# circuit.net
KiCad netlist of a schematic drawn in EAGLE
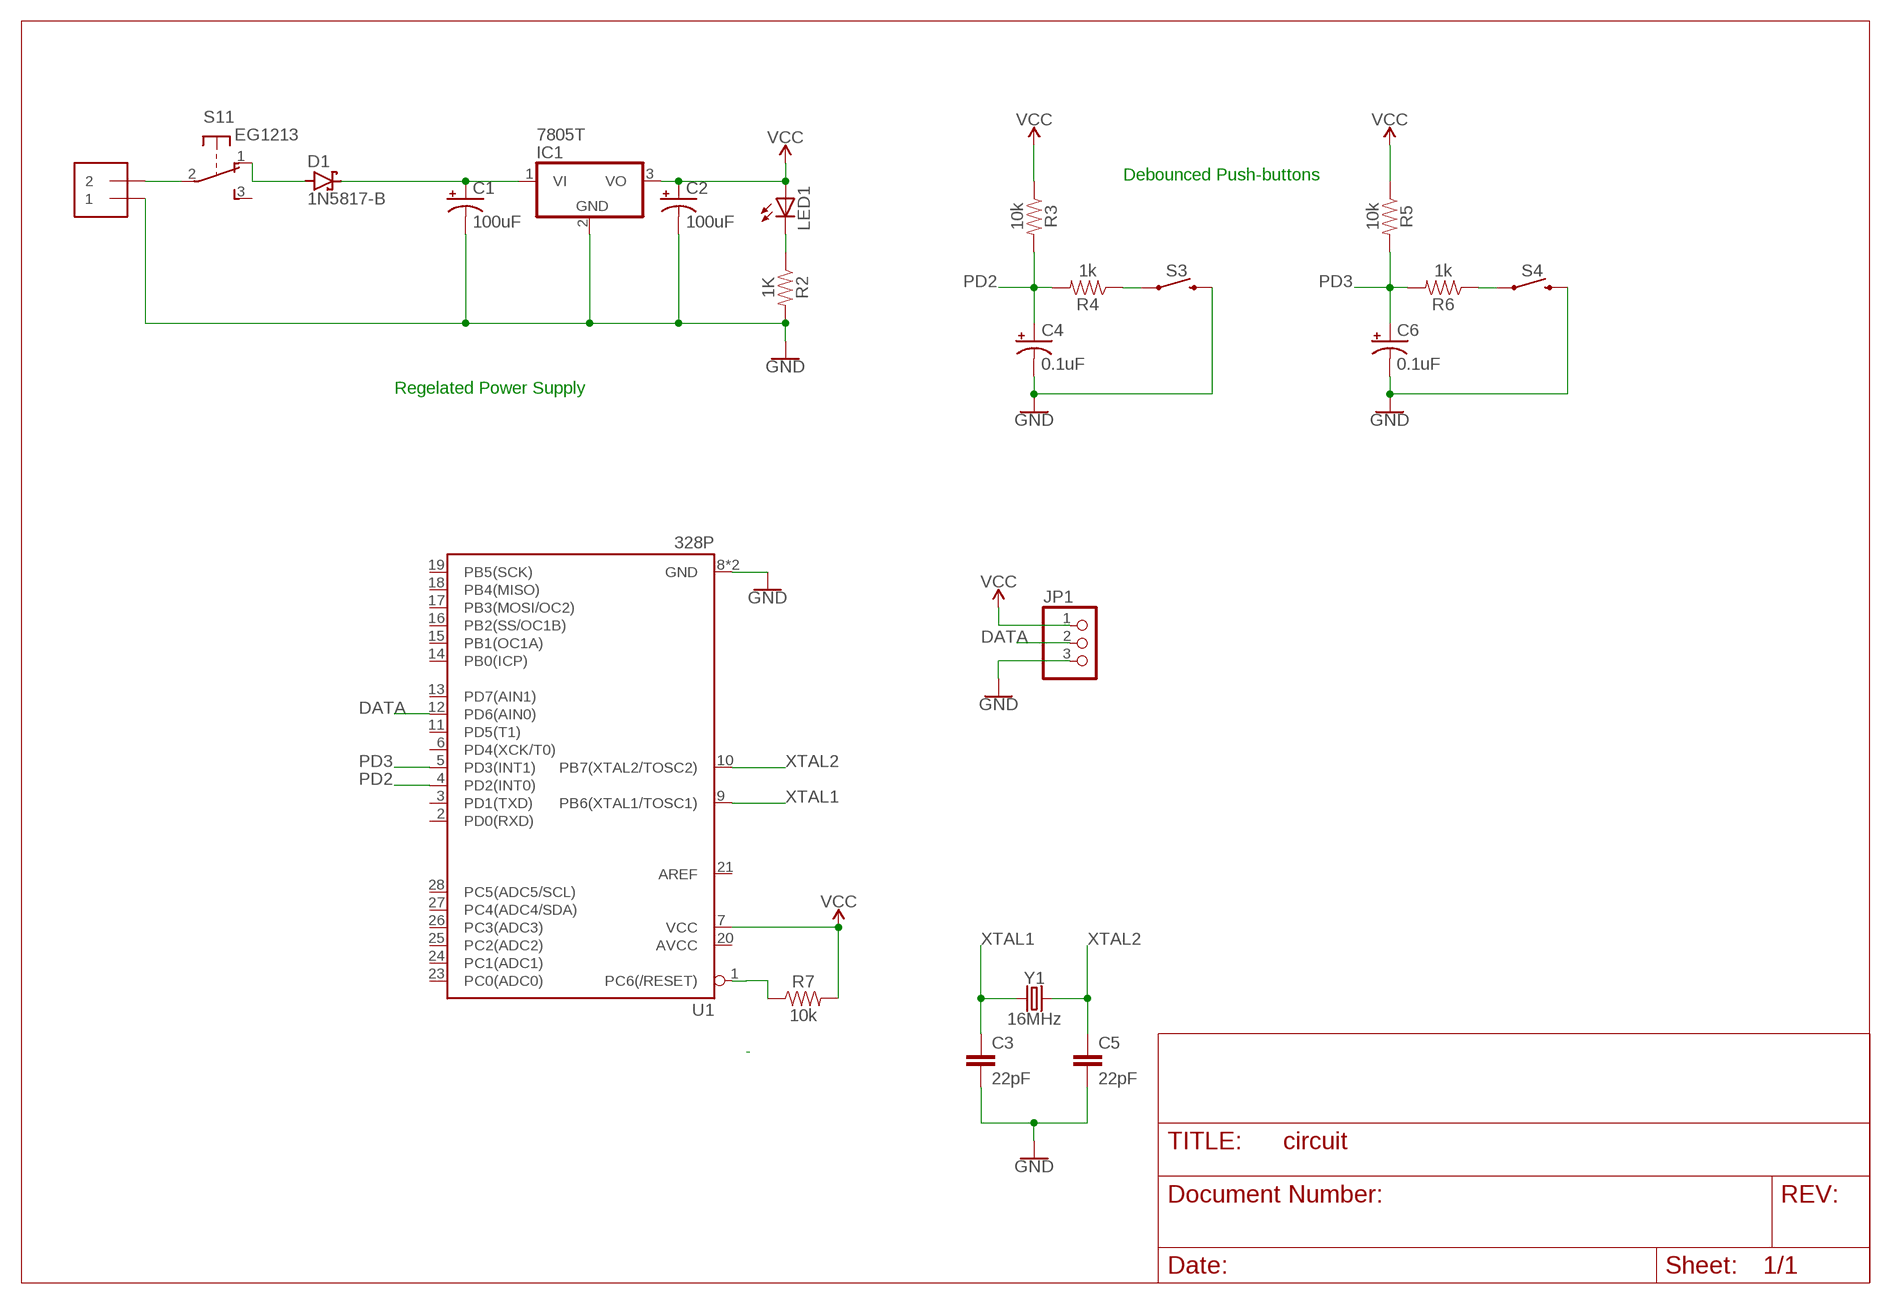
[diagram p0: schematic, sheet 1]

(export (version "E")
  (design (tool "Eeschema 10.0.6"))
  (components
    (comp (ref "C1")
      (value "100uF")
      (footprint "eagle-import:CPOL-RADIAL-2.5MM-6.5MM")
      (libsource (lib "eagle-import") (part "100UF-POLAR-RADIAL-2.5MM-25V-20%"))
    )
    (comp (ref "C2")
      (value "100uF")
      (footprint "eagle-import:CPOL-RADIAL-2.5MM-6.5MM")
      (libsource (lib "eagle-import") (part "100UF-POLAR-RADIAL-2.5MM-25V-20%"))
    )
    (comp (ref "C3")
      (value "22pF")
      (footprint "eagle-import:CAP-PTH-2.54")
      (libsource (lib "eagle-import") (part "22PF-PTH-2.54MM-200V-5%"))
    )
    (comp (ref "C4")
      (value "0.1uF")
      (footprint "eagle-import:CPOL-RADIAL-2.5MM-5MM")
      (libsource (lib "eagle-import") (part "10UF-POLAR-RADIAL-2.5MM-25V-20%"))
    )
    (comp (ref "C5")
      (value "22pF")
      (footprint "eagle-import:CAP-PTH-2.54")
      (libsource (lib "eagle-import") (part "22PF-PTH-2.54MM-200V-5%"))
    )
    (comp (ref "C6")
      (value "0.1uF")
      (footprint "eagle-import:CPOL-RADIAL-2.5MM-5MM")
      (libsource (lib "eagle-import") (part "10UF-POLAR-RADIAL-2.5MM-25V-20%"))
    )
    (comp (ref "D1")
      (value "1N5817-B")
      (footprint "eagle-import:DO41-7.6")
      (libsource (lib "eagle-import") (part "1N5817-B"))
    )
    (comp (ref "IC1")
      (value "7805T")
      (footprint "eagle-import:TO220H")
      (libsource (lib "eagle-import") (part "78T05"))
    )
    (comp (ref "J1")
      (value "1X2-3.5MM")
      (footprint "eagle-import:1X2-3.5MM")
      (libsource (lib "eagle-import") (part "1X2-3.5MM"))
    )
    (comp (ref "JP1")
      (value "PINHD-1X3")
      (footprint "eagle-import:1X03")
      (libsource (lib "eagle-import") (part "PINHD-1X3"))
    )
    (comp (ref "LED1")
      (value "LED3MM")
      (footprint "eagle-import:LED3MM")
      (libsource (lib "eagle-import") (part "LED3MM"))
    )
    (comp (ref "R2")
      (value "1K")
      (footprint "eagle-import:AXIAL-0.3")
      (libsource (lib "eagle-import") (part "RESISTORAXIAL-0.3"))
    )
    (comp (ref "R3")
      (value "10k")
      (footprint "eagle-import:AXIAL-0.3")
      (libsource (lib "eagle-import") (part "RESISTORAXIAL-0.3"))
    )
    (comp (ref "R4")
      (value "1k")
      (footprint "eagle-import:AXIAL-0.3")
      (libsource (lib "eagle-import") (part "RESISTORAXIAL-0.3"))
    )
    (comp (ref "R5")
      (value "10k")
      (footprint "eagle-import:AXIAL-0.3")
      (libsource (lib "eagle-import") (part "RESISTORAXIAL-0.3"))
    )
    (comp (ref "R6")
      (value "1k")
      (footprint "eagle-import:AXIAL-0.3")
      (libsource (lib "eagle-import") (part "RESISTORAXIAL-0.3"))
    )
    (comp (ref "R7")
      (value "10k")
      (footprint "eagle-import:AXIAL-0.3")
      (libsource (lib "eagle-import") (part "RESISTORAXIAL-0.3"))
    )
    (comp (ref "S1")
      (value "EG1213")
      (footprint "eagle-import:EG1213")
      (libsource (lib "eagle-import") (part "EG1213"))
    )
    (comp (ref "S3")
      (value "MOMENTARY-SWITCH-SPST-PTH-6.0MM")
      (footprint "eagle-import:TACTILE_SWITCH_PTH_6.0MM")
      (libsource (lib "eagle-import") (part "MOMENTARY-SWITCH-SPST-PTH-6.0MM"))
    )
    (comp (ref "S4")
      (value "MOMENTARY-SWITCH-SPST-PTH-6.0MM")
      (footprint "eagle-import:TACTILE_SWITCH_PTH_6.0MM")
      (libsource (lib "eagle-import") (part "MOMENTARY-SWITCH-SPST-PTH-6.0MM"))
    )
    (comp (ref "U1")
      (value "328P")
      (footprint "eagle-import:DIP28")
      (libsource (lib "eagle-import") (part "ATMEGA328P_PDIP"))
    )
    (comp (ref "Y1")
      (value "16MHz")
      (footprint "eagle-import:HC49US")
      (libsource (lib "eagle-import") (part "CRYSTAL-16MHZPTH-HC49US"))
    )
  )
  (nets
    (net (code "1") (name "/DATA") (class "Default")
      (node (ref "JP1") (pin "2") (pinfunction "2_2") (pintype "passive"))
      (node (ref "U1") (pin "12") (pinfunction "PD6(AIN0)_12") (pintype "bidirectional"))
    )
    (net (code "2") (name "/PD2") (class "Default")
      (node (ref "C4") (pin "1") (pinfunction "+_1") (pintype "passive"))
      (node (ref "R3") (pin "P$2") (pinfunction "2_P$2") (pintype "passive"))
      (node (ref "R4") (pin "P$2") (pinfunction "2_P$2") (pintype "passive"))
      (node (ref "U1") (pin "4") (pinfunction "PD2(INT0)_4") (pintype "bidirectional"))
    )
    (net (code "3") (name "/PD3") (class "Default")
      (node (ref "C6") (pin "1") (pinfunction "+_1") (pintype "passive"))
      (node (ref "R5") (pin "P$2") (pinfunction "2_P$2") (pintype "passive"))
      (node (ref "R6") (pin "P$2") (pinfunction "2_P$2") (pintype "passive"))
      (node (ref "U1") (pin "5") (pinfunction "PD3(INT1)_5") (pintype "bidirectional"))
    )
    (net (code "4") (name "/XTAL1") (class "Default")
      (node (ref "C3") (pin "1") (pinfunction "1_1") (pintype "passive"))
      (node (ref "U1") (pin "9") (pinfunction "PB6(XTAL1/TOSC1)_9") (pintype "bidirectional"))
      (node (ref "Y1") (pin "1") (pinfunction "1_1") (pintype "passive"))
    )
    (net (code "5") (name "/XTAL2") (class "Default")
      (node (ref "C5") (pin "1") (pinfunction "1_1") (pintype "passive"))
      (node (ref "U1") (pin "10") (pinfunction "PB7(XTAL2/TOSC2)_10") (pintype "bidirectional"))
      (node (ref "Y1") (pin "2") (pinfunction "2_2") (pintype "passive"))
    )
    (net (code "6") (name "GND") (class "Default")
      (node (ref "C1") (pin "2") (pinfunction "-_2") (pintype "passive"))
      (node (ref "C2") (pin "2") (pinfunction "-_2") (pintype "passive"))
      (node (ref "C3") (pin "2") (pinfunction "2_2") (pintype "passive"))
      (node (ref "C4") (pin "2") (pinfunction "-_2") (pintype "passive"))
      (node (ref "C5") (pin "2") (pinfunction "2_2") (pintype "passive"))
      (node (ref "C6") (pin "2") (pinfunction "-_2") (pintype "passive"))
      (node (ref "IC1") (pin "2") (pinfunction "GND_2") (pintype "passive"))
      (node (ref "J1") (pin "1") (pinfunction "1_1") (pintype "passive"))
      (node (ref "JP1") (pin "3") (pinfunction "3_3") (pintype "passive"))
      (node (ref "R2") (pin "P$2") (pinfunction "2_P$2") (pintype "passive"))
      (node (ref "S3") (pin "3") (pinfunction "2_3") (pintype "passive"))
      (node (ref "S4") (pin "3") (pinfunction "2_3") (pintype "passive"))
      (node (ref "U1") (pin "22") (pinfunction "GND_22") (pintype "bidirectional"))
      (node (ref "U1") (pin "8") (pinfunction "GND_8") (pintype "bidirectional"))
    )
    (net (code "7") (name "Net-(C1-+)") (class "Default")
      (node (ref "C1") (pin "1") (pinfunction "+_1") (pintype "passive"))
      (node (ref "D1") (pin "C") (pinfunction "C_C") (pintype "passive"))
      (node (ref "IC1") (pin "1") (pinfunction "VI_1") (pintype "input"))
    )
    (net (code "8") (name "Net-(LED1-C)") (class "Default")
      (node (ref "LED1") (pin "K") (pinfunction "C_K") (pintype "passive"))
      (node (ref "R2") (pin "P$1") (pinfunction "1_P$1") (pintype "passive"))
    )
    (net (code "9") (name "Net-(R4-1)") (class "Default")
      (node (ref "R4") (pin "P$1") (pinfunction "1_P$1") (pintype "passive"))
      (node (ref "S3") (pin "1") (pinfunction "1_1") (pintype "passive"))
    )
    (net (code "10") (name "Net-(R6-1)") (class "Default")
      (node (ref "R6") (pin "P$1") (pinfunction "1_P$1") (pintype "passive"))
      (node (ref "S4") (pin "1") (pinfunction "1_1") (pintype "passive"))
    )
    (net (code "11") (name "Net-(R7-1)") (class "Default")
      (node (ref "R7") (pin "P$1") (pinfunction "1_P$1") (pintype "passive"))
      (node (ref "U1") (pin "1") (pinfunction "PC6(/RESET)_1") (pintype "bidirectional"))
    )
    (net (code "12") (name "Net-(S1A-O)") (class "Default")
      (node (ref "D1") (pin "A") (pinfunction "A_A") (pintype "passive"))
      (node (ref "S1") (pin "1") (pinfunction "O_1") (pintype "passive"))
    )
    (net (code "13") (name "Net-(S1A-P)") (class "Default")
      (node (ref "J1") (pin "2") (pinfunction "2_2") (pintype "passive"))
      (node (ref "S1") (pin "2") (pinfunction "P_2") (pintype "passive"))
    )
    (net (code "14") (name "VCC") (class "Default")
      (node (ref "C2") (pin "1") (pinfunction "+_1") (pintype "passive"))
      (node (ref "IC1") (pin "3") (pinfunction "VO_3") (pintype "passive"))
      (node (ref "JP1") (pin "1") (pinfunction "1_1") (pintype "passive"))
      (node (ref "LED1") (pin "A") (pinfunction "A_A") (pintype "passive"))
      (node (ref "R3") (pin "P$1") (pinfunction "1_P$1") (pintype "passive"))
      (node (ref "R5") (pin "P$1") (pinfunction "1_P$1") (pintype "passive"))
      (node (ref "R7") (pin "P$2") (pinfunction "2_P$2") (pintype "passive"))
      (node (ref "U1") (pin "7") (pinfunction "VCC_7") (pintype "bidirectional"))
    )
    (net (code "15") (name "unconnected-(S1A-S-Pad3)") (class "Default")
      (node (ref "S1") (pin "3") (pinfunction "S_3") (pintype "passive"))
    )
    (net (code "16") (name "unconnected-(U1-AREF-Pad21)") (class "Default")
      (node (ref "U1") (pin "21") (pinfunction "AREF_21") (pintype "bidirectional"))
    )
    (net (code "17") (name "unconnected-(U1-AVCC-Pad20)") (class "Default")
      (node (ref "U1") (pin "20") (pinfunction "AVCC_20") (pintype "bidirectional"))
    )
    (net (code "18") (name "unconnected-(U1-PB0(ICP)-Pad14)") (class "Default")
      (node (ref "U1") (pin "14") (pinfunction "PB0(ICP)_14") (pintype "bidirectional"))
    )
    (net (code "19") (name "unconnected-(U1-PB1(OC1A)-Pad15)") (class "Default")
      (node (ref "U1") (pin "15") (pinfunction "PB1(OC1A)_15") (pintype "bidirectional"))
    )
    (net (code "20") (name "unconnected-(U1-PB2(SS{slash}OC1B)-Pad16)") (class "Default")
      (node (ref "U1") (pin "16") (pinfunction "PB2(SS/OC1B)_16") (pintype "bidirectional"))
    )
    (net (code "21") (name "unconnected-(U1-PB3(MOSI{slash}OC2)-Pad17)") (class "Default")
      (node (ref "U1") (pin "17") (pinfunction "PB3(MOSI/OC2)_17") (pintype "bidirectional"))
    )
    (net (code "22") (name "unconnected-(U1-PB4(MISO)-Pad18)") (class "Default")
      (node (ref "U1") (pin "18") (pinfunction "PB4(MISO)_18") (pintype "bidirectional"))
    )
    (net (code "23") (name "unconnected-(U1-PB5(SCK)-Pad19)") (class "Default")
      (node (ref "U1") (pin "19") (pinfunction "PB5(SCK)_19") (pintype "bidirectional"))
    )
    (net (code "24") (name "unconnected-(U1-PC0(ADC0)-Pad23)") (class "Default")
      (node (ref "U1") (pin "23") (pinfunction "PC0(ADC0)_23") (pintype "bidirectional"))
    )
    (net (code "25") (name "unconnected-(U1-PC1(ADC1)-Pad24)") (class "Default")
      (node (ref "U1") (pin "24") (pinfunction "PC1(ADC1)_24") (pintype "bidirectional"))
    )
    (net (code "26") (name "unconnected-(U1-PC2(ADC2)-Pad25)") (class "Default")
      (node (ref "U1") (pin "25") (pinfunction "PC2(ADC2)_25") (pintype "bidirectional"))
    )
    (net (code "27") (name "unconnected-(U1-PC3(ADC3)-Pad26)") (class "Default")
      (node (ref "U1") (pin "26") (pinfunction "PC3(ADC3)_26") (pintype "bidirectional"))
    )
    (net (code "28") (name "unconnected-(U1-PC4(ADC4{slash}SDA)-Pad27)") (class "Default")
      (node (ref "U1") (pin "27") (pinfunction "PC4(ADC4/SDA)_27") (pintype "bidirectional"))
    )
    (net (code "29") (name "unconnected-(U1-PC5(ADC5{slash}SCL)-Pad28)") (class "Default")
      (node (ref "U1") (pin "28") (pinfunction "PC5(ADC5/SCL)_28") (pintype "bidirectional"))
    )
    (net (code "30") (name "unconnected-(U1-PD0(RXD)-Pad2)") (class "Default")
      (node (ref "U1") (pin "2") (pinfunction "PD0(RXD)_2") (pintype "bidirectional"))
    )
    (net (code "31") (name "unconnected-(U1-PD1(TXD)-Pad3)") (class "Default")
      (node (ref "U1") (pin "3") (pinfunction "PD1(TXD)_3") (pintype "bidirectional"))
    )
    (net (code "32") (name "unconnected-(U1-PD4(XCK{slash}T0)-Pad6)") (class "Default")
      (node (ref "U1") (pin "6") (pinfunction "PD4(XCK/T0)_6") (pintype "bidirectional"))
    )
    (net (code "33") (name "unconnected-(U1-PD5(T1)-Pad11)") (class "Default")
      (node (ref "U1") (pin "11") (pinfunction "PD5(T1)_11") (pintype "bidirectional"))
    )
    (net (code "34") (name "unconnected-(U1-PD7(AIN1)-Pad13)") (class "Default")
      (node (ref "U1") (pin "13") (pinfunction "PD7(AIN1)_13") (pintype "bidirectional"))
    )
  )
)
